# 0008-NSA_IR_Sync_Board.net
KiCad netlist of a schematic drawn in Altium Designer
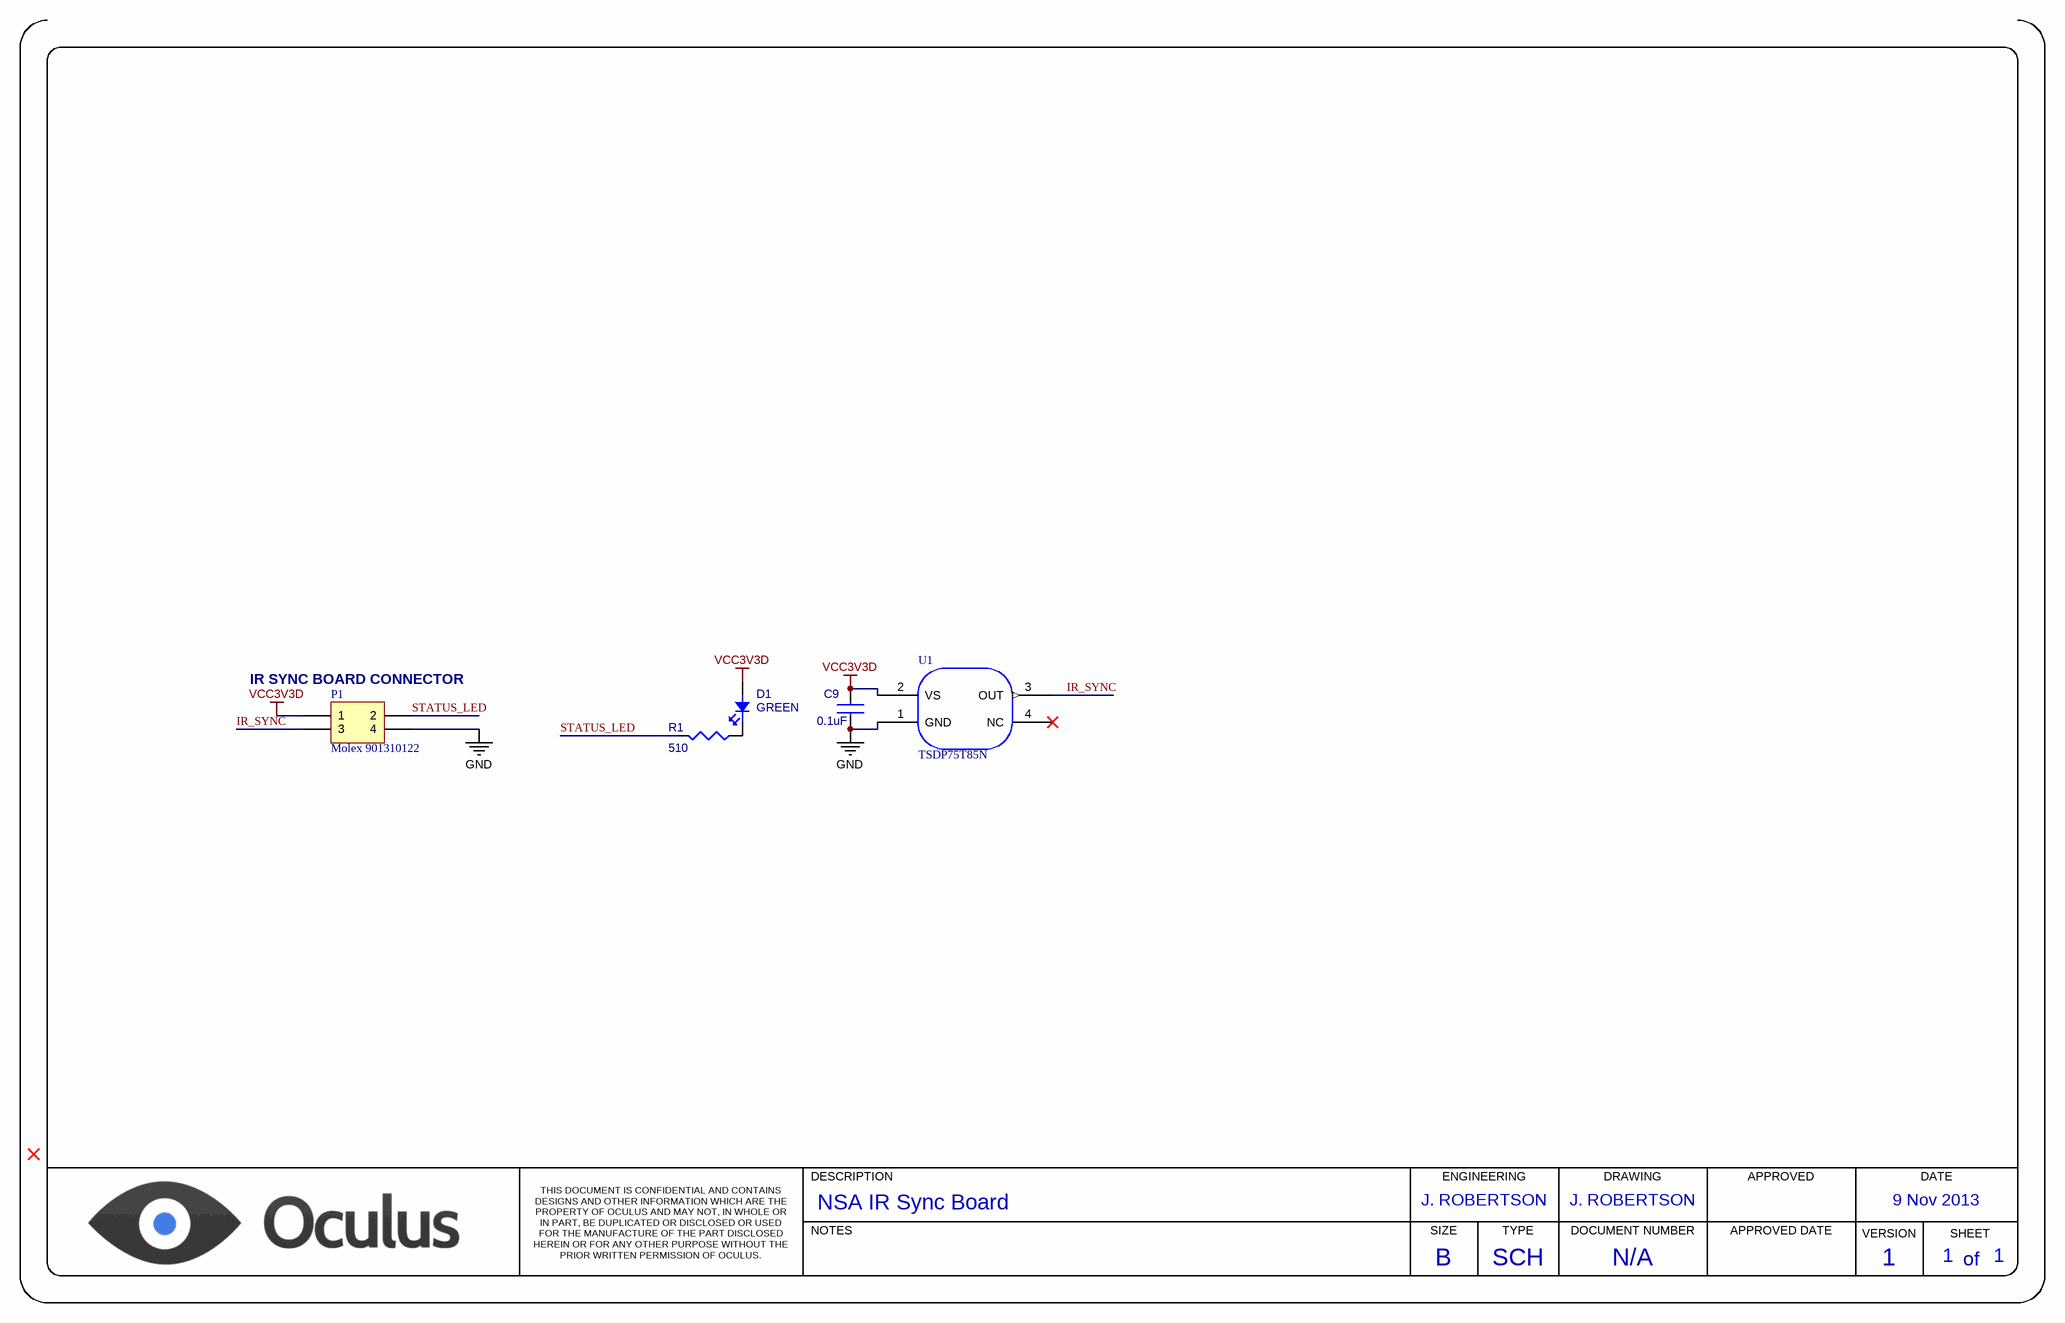
[diagram p0: 0008-NSA_IR_Sync_Board.SchDoc]

(export (version "E")
  (design (tool "Eeschema 10.0.6"))
  (components
    (comp (ref "C9")
      (value "0.1uF")
      (footprint "RESISTOR_0603")
      (description "CAP CER 0.1UF 6.3V 20% X5R 0402")
      (libsource (lib "SchematicComponents") (part "CAP, CERAMIC"))
    )
    (comp (ref "D1")
      (value "LED")
      (footprint "LED_GREEN_0603")
      (description "LED, GREEN, 0603")
      (fields (field (name "COLOR") "GREEN"))
      (libsource (lib "CP1") (part "LED"))
    )
    (comp (ref "P1")
      (value "Molex 901310122")
      (footprint "90131-0122")
      (description "CONN HEADER 4POS .100\" STR TIN")
      (libsource (lib "Miscellaneous Connectors") (part "Header 2X2"))
    )
    (comp (ref "R1")
      (value "510")
      (footprint "RESISTOR_0603")
      (description "RES 510 OHM 1/10W 1% 0603 SMD")
      (libsource (lib "SchematicComponents") (part "RESISTOR"))
    )
    (comp (ref "U1")
      (value "TSDP75T85N")
      (footprint "TSDP75T85N")
      (description "IR Receiver Modules for Remote Control Systems")
      (libsource (lib "0008-NSA_IR_Sync_Board") (part "TSDP75T85N"))
    )
  )
  (nets
    (net (code "1") (name "/IR_SYNC") (class "Default")
      (node (ref "P1") (pin "3") (pinfunction "3_3") (pintype "passive"))
      (node (ref "U1") (pin "3") (pinfunction "OUT_3") (pintype "output"))
    )
    (net (code "2") (name "/STATUS_LED") (class "Default")
      (node (ref "P1") (pin "2") (pinfunction "2_2") (pintype "passive"))
      (node (ref "R1") (pin "2") (pinfunction "2_2") (pintype "passive"))
    )
    (net (code "3") (name "GND") (class "Default")
      (node (ref "C9") (pin "2") (pinfunction "2_2") (pintype "passive"))
      (node (ref "P1") (pin "4") (pinfunction "4_4") (pintype "passive"))
      (node (ref "U1") (pin "1") (pinfunction "GND_1") (pintype "power_in"))
    )
    (net (code "4") (name "Net-(D1-K)") (class "Default")
      (node (ref "D1") (pin "2") (pinfunction "K_2") (pintype "passive"))
      (node (ref "R1") (pin "1") (pinfunction "1_1") (pintype "passive"))
    )
    (net (code "5") (name "VCC3V3D") (class "Default")
      (node (ref "C9") (pin "1") (pinfunction "1_1") (pintype "passive"))
      (node (ref "D1") (pin "1") (pinfunction "A_1") (pintype "passive"))
      (node (ref "P1") (pin "1") (pinfunction "1_1") (pintype "passive"))
      (node (ref "U1") (pin "2") (pinfunction "VS_2") (pintype "power_in"))
    )
    (net (code "6") (name "unconnected-(U1-NC-Pad4)") (class "Default")
      (node (ref "U1") (pin "4") (pinfunction "NC_4") (pintype "passive+no_connect"))
    )
  )
)
